# SensorTile_PC.net
KiCad netlist of a schematic drawn in EAGLE
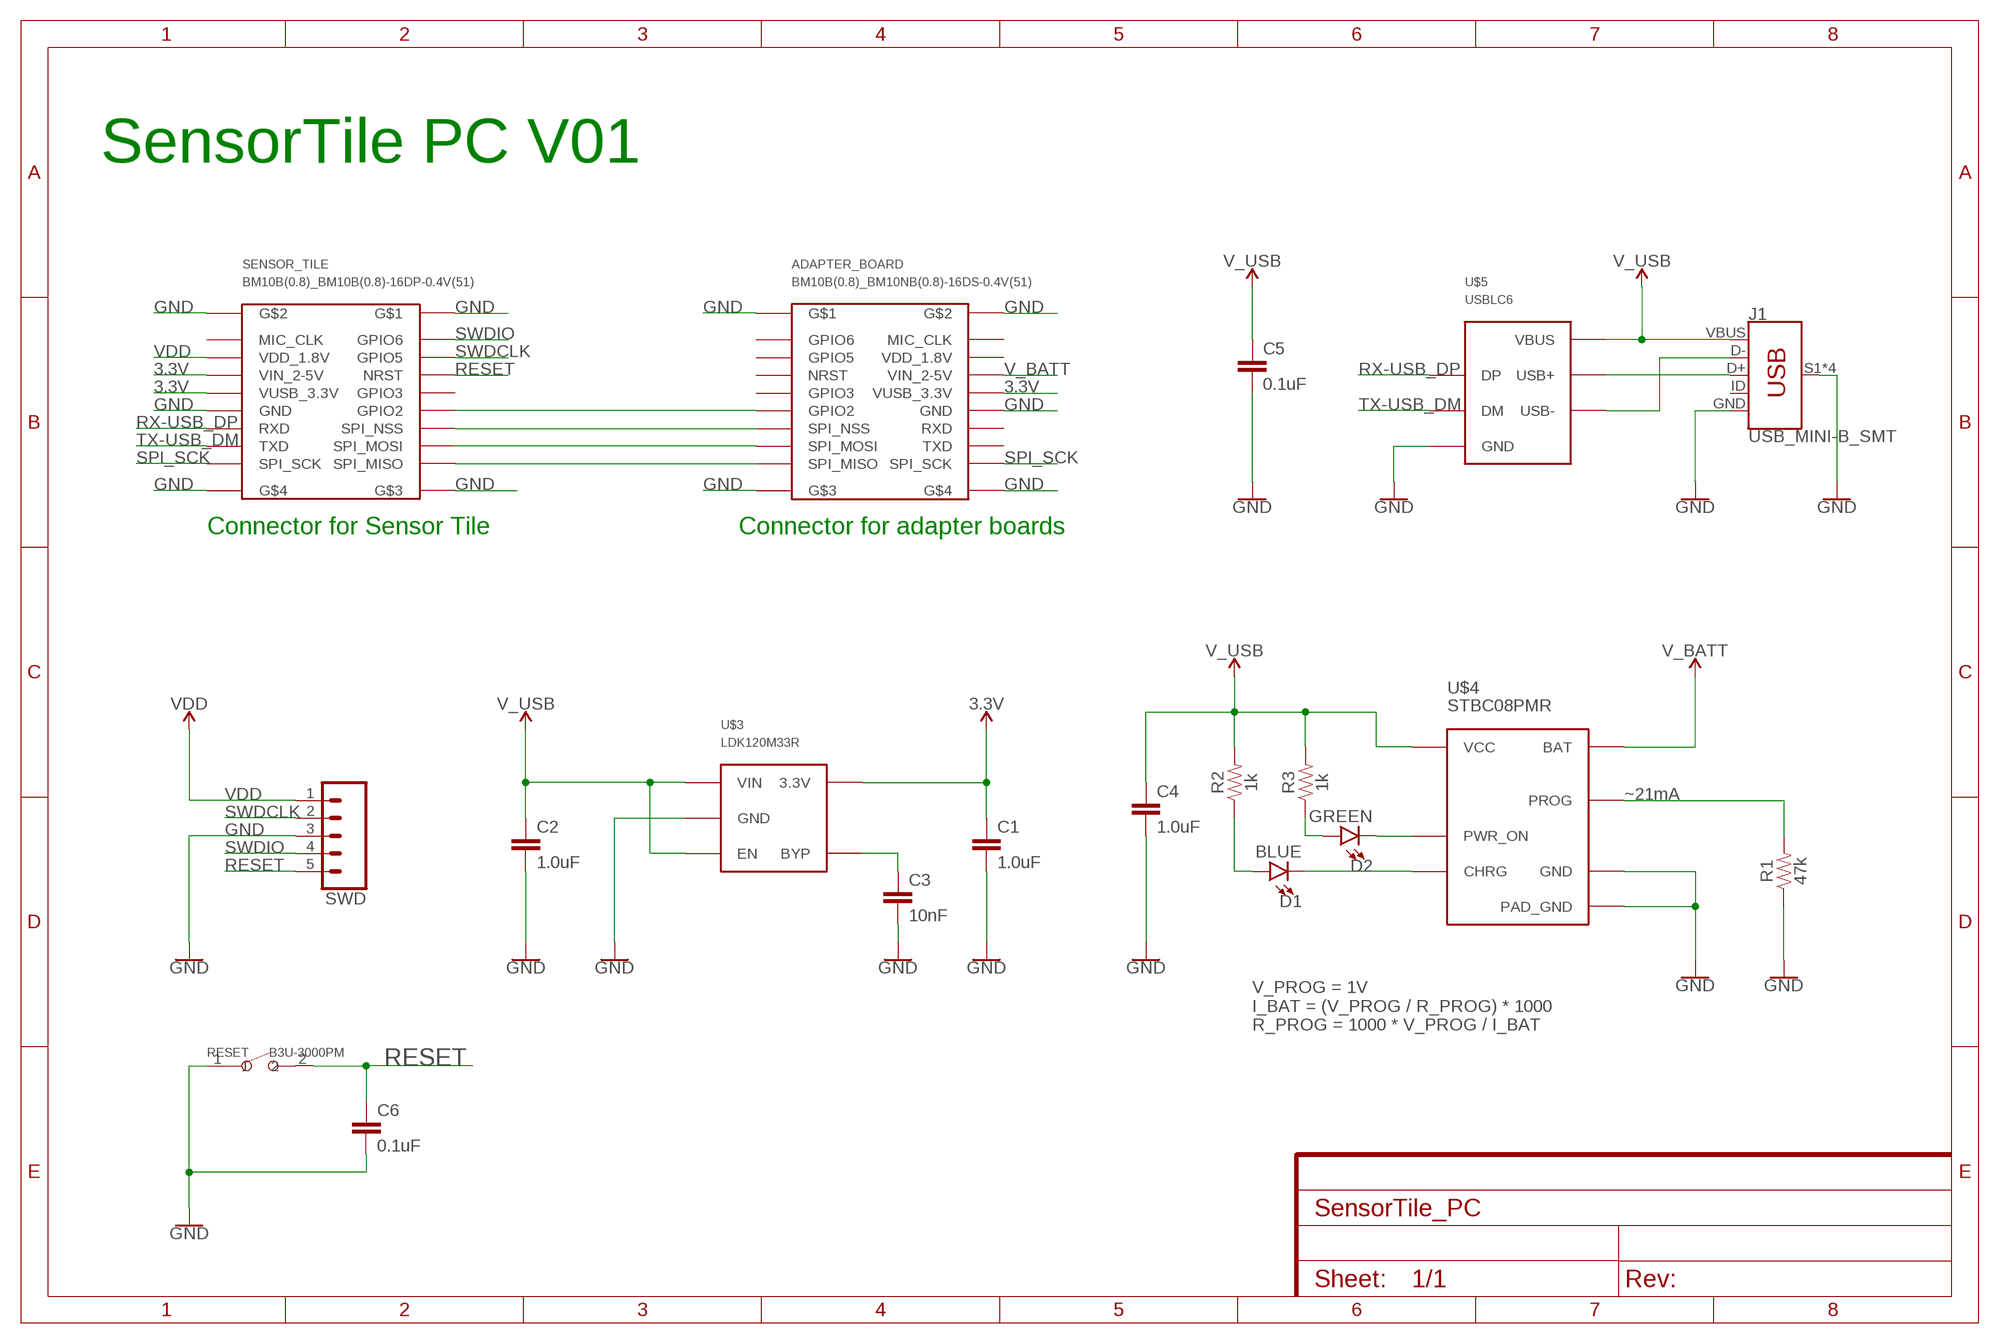
[diagram p0: schematic, sheet 1]

(export (version "E")
  (design (tool "Eeschema 10.0.6"))
  (components
    (comp (ref "ADAPTER_BOARD")
      (value "BM10B(0.8)_BM10NB(0.8)-16DS-0.4V(51)")
      (footprint "eagle-import:BM10B(0.8)_BM10NB(0.8)-16DS-0.4V(51)")
      (libsource (lib "eagle-import") (part "BM10B(0.8)_BM10NB(0.8)-16DS-0.4V(51)"))
    )
    (comp (ref "C1")
      (value "1.0uF")
      (footprint "eagle-import:0603")
      (libsource (lib "eagle-import") (part "1.0UF-0603-16V-10%"))
    )
    (comp (ref "C2")
      (value "1.0uF")
      (footprint "eagle-import:0603")
      (libsource (lib "eagle-import") (part "1.0UF-0603-16V-10%"))
    )
    (comp (ref "C3")
      (value "10nF")
      (footprint "eagle-import:0603")
      (libsource (lib "eagle-import") (part "10NF-0603-50V-10%"))
    )
    (comp (ref "C4")
      (value "1.0uF")
      (footprint "eagle-import:0603")
      (libsource (lib "eagle-import") (part "1.0UF-0603-16V-10%"))
    )
    (comp (ref "C5")
      (value "0.1uF")
      (footprint "eagle-import:0603")
      (libsource (lib "eagle-import") (part "0.1UF-0603-25V-5%"))
    )
    (comp (ref "C6")
      (value "0.1uF")
      (footprint "eagle-import:0603")
      (libsource (lib "eagle-import") (part "0.1UF-0603-25V-5%"))
    )
    (comp (ref "D1")
      (value "BLUE")
      (footprint "eagle-import:LED-0603")
      (libsource (lib "eagle-import") (part "LED-BLUE0603"))
    )
    (comp (ref "D2")
      (value "GREEN")
      (footprint "eagle-import:LED-0603")
      (libsource (lib "eagle-import") (part "LED-GREEN0603"))
    )
    (comp (ref "J1")
      (value "USB_MINI-B_SMT")
      (footprint "eagle-import:USB-MINIB")
      (libsource (lib "eagle-import") (part "USB_MINI-B_SMT"))
    )
    (comp (ref "R1")
      (value "47k")
      (footprint "eagle-import:0603")
      (libsource (lib "eagle-import") (part "47KOHM-0603-1/10W-1%"))
    )
    (comp (ref "R2")
      (value "1k")
      (footprint "eagle-import:0603")
      (libsource (lib "eagle-import") (part "1KOHM-0603-1/10W-1%"))
    )
    (comp (ref "R3")
      (value "1k")
      (footprint "eagle-import:0603")
      (libsource (lib "eagle-import") (part "1KOHM-0603-1/10W-1%"))
    )
    (comp (ref "RESET")
      (value "B3U-3000PM")
      (footprint "eagle-import:SW2-2.6-3.0X2.5X1.2+0.4MM")
      (fields (field (name "MPN") "B3U-1000P-2P-SMD"))
      (libsource (lib "eagle-import") (part "SMD-BUTTON(2P-3.0X2.5X1.2+0.4MM)-B3U-1000P-2P-SMD"))
    )
    (comp (ref "SENSOR_TILE")
      (value "BM10B(0.8)_BM10B(0.8)-16DP-0.4V(51)")
      (footprint "eagle-import:BM10B(0.8)_BM10B(0.8)-16DP-0.4V(51)")
      (libsource (lib "eagle-import") (part "BM10B(0.8)_BM10B(0.8)-16DP-0.4V(51)"))
    )
    (comp (ref "SWD")
      (value "CONN_05")
      (footprint "eagle-import:1X05")
      (libsource (lib "eagle-import") (part "CONN_05"))
    )
    (comp (ref "U$3")
      (value "LDK120M33R")
      (footprint "eagle-import:SOT23-5")
      (libsource (lib "eagle-import") (part "LDK120M33R"))
    )
    (comp (ref "U$4")
      (value "STBC08PMR")
      (footprint "eagle-import:6-DFN(3X3)")
      (libsource (lib "eagle-import") (part "STBC08PMR"))
    )
    (comp (ref "U$5")
      (value "USBLC6")
      (footprint "eagle-import:SOT23-6L")
      (libsource (lib "eagle-import") (part "USBLC6-2SC6"))
    )
  )
  (nets
    (net (code "1") (name "/RESET") (class "Default")
      (node (ref "C6") (pin "1") (pinfunction "1_1") (pintype "passive"))
      (node (ref "RESET") (pin "2") (pinfunction "2_2") (pintype "bidirectional"))
      (node (ref "SENSOR_TILE") (pin "NRST") (pinfunction "NRST_NRST") (pintype "bidirectional"))
      (node (ref "SWD") (pin "5") (pinfunction "5_5") (pintype "passive"))
    )
    (net (code "2") (name "/RX-USB_DP") (class "Default")
      (node (ref "SENSOR_TILE") (pin "RXD") (pinfunction "RXD_RXD") (pintype "bidirectional"))
      (node (ref "U$5") (pin "D+IN$1") (pinfunction "DP_D+IN$1") (pintype "bidirectional"))
    )
    (net (code "3") (name "/SPI_SCK") (class "Default")
      (node (ref "ADAPTER_BOARD") (pin "SPI_SCK") (pinfunction "SPI_SCK_SPI_SCK") (pintype "bidirectional"))
      (node (ref "SENSOR_TILE") (pin "SPI_SCK") (pinfunction "SPI_SCK_SPI_SCK") (pintype "bidirectional"))
    )
    (net (code "4") (name "/SWDCLK") (class "Default")
      (node (ref "SENSOR_TILE") (pin "GPIO5") (pinfunction "GPIO5_GPIO5") (pintype "bidirectional"))
      (node (ref "SWD") (pin "2") (pinfunction "2_2") (pintype "passive"))
    )
    (net (code "5") (name "/SWDIO") (class "Default")
      (node (ref "SENSOR_TILE") (pin "GPIO6") (pinfunction "GPIO6_GPIO6") (pintype "bidirectional"))
      (node (ref "SWD") (pin "4") (pinfunction "4_4") (pintype "passive"))
    )
    (net (code "6") (name "/TX-USB_DM") (class "Default")
      (node (ref "SENSOR_TILE") (pin "TXD") (pinfunction "TXD_TXD") (pintype "bidirectional"))
      (node (ref "U$5") (pin "D-IN$3") (pinfunction "DM_D-IN$3") (pintype "bidirectional"))
    )
    (net (code "7") (name "3.3V") (class "Default")
      (node (ref "ADAPTER_BOARD") (pin "VUSB_3.3V") (pinfunction "VUSB_3.3V_VUSB_3.3V") (pintype "bidirectional"))
      (node (ref "C1") (pin "1") (pinfunction "1_1") (pintype "passive"))
      (node (ref "SENSOR_TILE") (pin "VIN_2-5V") (pinfunction "VIN_2-5V_VIN_2-5V") (pintype "bidirectional"))
      (node (ref "SENSOR_TILE") (pin "VUSB_3.3V") (pinfunction "VUSB_3.3V_VUSB_3.3V") (pintype "bidirectional"))
      (node (ref "U$3") (pin "3V3&5") (pinfunction "3.3V_3V3&5") (pintype "bidirectional"))
    )
    (net (code "8") (name "GND") (class "Default")
      (node (ref "ADAPTER_BOARD") (pin "G$1") (pinfunction "G$1_G$1") (pintype "bidirectional"))
      (node (ref "ADAPTER_BOARD") (pin "G$2") (pinfunction "G$2_G$2") (pintype "bidirectional"))
      (node (ref "ADAPTER_BOARD") (pin "G$3") (pinfunction "G$3_G$3") (pintype "bidirectional"))
      (node (ref "ADAPTER_BOARD") (pin "G$4") (pinfunction "G$4_G$4") (pintype "bidirectional"))
      (node (ref "ADAPTER_BOARD") (pin "GND$1") (pinfunction "GND_GND$1") (pintype "bidirectional"))
      (node (ref "C1") (pin "2") (pinfunction "2_2") (pintype "passive"))
      (node (ref "C2") (pin "2") (pinfunction "2_2") (pintype "passive"))
      (node (ref "C3") (pin "2") (pinfunction "2_2") (pintype "passive"))
      (node (ref "C4") (pin "2") (pinfunction "2_2") (pintype "passive"))
      (node (ref "C5") (pin "2") (pinfunction "2_2") (pintype "passive"))
      (node (ref "C6") (pin "2") (pinfunction "2_2") (pintype "passive"))
      (node (ref "J1") (pin "GND") (pinfunction "GND_GND") (pintype "power_in"))
      (node (ref "J1") (pin "S1") (pinfunction "SHIELD_S1") (pintype "bidirectional"))
      (node (ref "J1") (pin "S2") (pinfunction "SHIELD_S2") (pintype "bidirectional"))
      (node (ref "J1") (pin "S3") (pinfunction "SHIELD_S3") (pintype "bidirectional"))
      (node (ref "J1") (pin "S4") (pinfunction "SHIELD_S4") (pintype "bidirectional"))
      (node (ref "R1") (pin "1") (pinfunction "1_1") (pintype "passive"))
      (node (ref "RESET") (pin "1") (pinfunction "1_1") (pintype "bidirectional"))
      (node (ref "SENSOR_TILE") (pin "G$1") (pinfunction "G$1_G$1") (pintype "bidirectional"))
      (node (ref "SENSOR_TILE") (pin "G$2") (pinfunction "G$2_G$2") (pintype "bidirectional"))
      (node (ref "SENSOR_TILE") (pin "G$3") (pinfunction "G$3_G$3") (pintype "bidirectional"))
      (node (ref "SENSOR_TILE") (pin "G$4") (pinfunction "G$4_G$4") (pintype "bidirectional"))
      (node (ref "SENSOR_TILE") (pin "GND$1") (pinfunction "GND_GND$1") (pintype "bidirectional"))
      (node (ref "SWD") (pin "3") (pinfunction "3_3") (pintype "passive"))
      (node (ref "U$3") (pin "GND$2") (pinfunction "GND_GND$2") (pintype "bidirectional"))
      (node (ref "U$4") (pin "GND$4") (pinfunction "GND_GND$4") (pintype "bidirectional"))
      (node (ref "U$4") (pin "PAD_GND$7") (pinfunction "PAD_GND_PAD_GND$7") (pintype "bidirectional"))
      (node (ref "U$5") (pin "GND$2") (pinfunction "GND_GND$2") (pintype "bidirectional"))
    )
    (net (code "9") (name "Net-(ADAPTER_BOARD-PadGPIO2)") (class "Default")
      (node (ref "ADAPTER_BOARD") (pin "GPIO2") (pinfunction "GPIO2_GPIO2") (pintype "bidirectional"))
      (node (ref "SENSOR_TILE") (pin "GPIO2") (pinfunction "GPIO2_GPIO2") (pintype "bidirectional"))
    )
    (net (code "10") (name "Net-(ADAPTER_BOARD-PadSPI_MISO)") (class "Default")
      (node (ref "ADAPTER_BOARD") (pin "SPI_MISO") (pinfunction "SPI_MISO_SPI_MISO") (pintype "bidirectional"))
      (node (ref "SENSOR_TILE") (pin "SPI_MISO") (pinfunction "SPI_MISO_SPI_MISO") (pintype "bidirectional"))
    )
    (net (code "11") (name "Net-(ADAPTER_BOARD-PadSPI_MOSI)") (class "Default")
      (node (ref "ADAPTER_BOARD") (pin "SPI_MOSI") (pinfunction "SPI_MOSI_SPI_MOSI") (pintype "bidirectional"))
      (node (ref "SENSOR_TILE") (pin "SPI_MOSI") (pinfunction "SPI_MOSI_SPI_MOSI") (pintype "bidirectional"))
    )
    (net (code "12") (name "Net-(ADAPTER_BOARD-PadSPI_NSS)") (class "Default")
      (node (ref "ADAPTER_BOARD") (pin "SPI_NSS") (pinfunction "SPI_NSS_SPI_NSS") (pintype "bidirectional"))
      (node (ref "SENSOR_TILE") (pin "SPI_NSS") (pinfunction "SPI_NSS_SPI_NSS") (pintype "bidirectional"))
    )
    (net (code "13") (name "Net-(D1-PadA)") (class "Default")
      (node (ref "D1") (pin "A") (pinfunction "A_A") (pintype "passive"))
      (node (ref "R2") (pin "1") (pinfunction "1_1") (pintype "passive"))
    )
    (net (code "14") (name "Net-(D2-PadA)") (class "Default")
      (node (ref "D2") (pin "A") (pinfunction "A_A") (pintype "passive"))
      (node (ref "R3") (pin "1") (pinfunction "1_1") (pintype "passive"))
    )
    (net (code "15") (name "Net-(U$3-BYP)") (class "Default")
      (node (ref "C3") (pin "1") (pinfunction "1_1") (pintype "passive"))
      (node (ref "U$3") (pin "BYP$4") (pinfunction "BYP_BYP$4") (pintype "bidirectional"))
    )
    (net (code "16") (name "Net-(U$4-CHRG)") (class "Default")
      (node (ref "D1") (pin "C") (pinfunction "C_C") (pintype "passive"))
      (node (ref "U$4") (pin "CHRG$3") (pinfunction "CHRG_CHRG$3") (pintype "bidirectional"))
    )
    (net (code "17") (name "Net-(U$4-PROG)") (class "Default")
      (node (ref "R1") (pin "2") (pinfunction "2_2") (pintype "passive"))
      (node (ref "U$4") (pin "PROG$5") (pinfunction "PROG_PROG$5") (pintype "bidirectional"))
    )
    (net (code "18") (name "Net-(U$4-PWR_ON)") (class "Default")
      (node (ref "D2") (pin "C") (pinfunction "C_C") (pintype "passive"))
      (node (ref "U$4") (pin "ON$2") (pinfunction "PWR_ON_ON$2") (pintype "bidirectional"))
    )
    (net (code "19") (name "Net-(U$5-USB+)") (class "Default")
      (node (ref "J1") (pin "D+") (pinfunction "D+_D+") (pintype "bidirectional"))
      (node (ref "U$5") (pin "D+OUT$1$6") (pinfunction "USB+_D+OUT$1$6") (pintype "bidirectional"))
    )
    (net (code "20") (name "Net-(U$5-USB-)") (class "Default")
      (node (ref "J1") (pin "D-") (pinfunction "D-_D-") (pintype "bidirectional"))
      (node (ref "U$5") (pin "D-OUT$1$4") (pinfunction "USB-_D-OUT$1$4") (pintype "bidirectional"))
    )
    (net (code "21") (name "VDD") (class "Default")
      (node (ref "SENSOR_TILE") (pin "VDD_1.8V") (pinfunction "VDD_1.8V_VDD_1.8V") (pintype "bidirectional"))
      (node (ref "SWD") (pin "1") (pinfunction "1_1") (pintype "passive"))
    )
    (net (code "22") (name "V_BATT") (class "Default")
      (node (ref "ADAPTER_BOARD") (pin "VIN_2-5V") (pinfunction "VIN_2-5V_VIN_2-5V") (pintype "bidirectional"))
      (node (ref "U$4") (pin "BAT$1") (pinfunction "BAT_BAT$1") (pintype "bidirectional"))
    )
    (net (code "23") (name "V_USB") (class "Default")
      (node (ref "C2") (pin "1") (pinfunction "1_1") (pintype "passive"))
      (node (ref "C4") (pin "1") (pinfunction "1_1") (pintype "passive"))
      (node (ref "C5") (pin "1") (pinfunction "1_1") (pintype "passive"))
      (node (ref "J1") (pin "VBUS") (pinfunction "VBUS_VBUS") (pintype "power_in"))
      (node (ref "R2") (pin "2") (pinfunction "2_2") (pintype "passive"))
      (node (ref "R3") (pin "2") (pinfunction "2_2") (pintype "passive"))
      (node (ref "U$3") (pin "EN$3") (pinfunction "EN_EN$3") (pintype "bidirectional"))
      (node (ref "U$3") (pin "VIN$1") (pinfunction "VIN_VIN$1") (pintype "bidirectional"))
      (node (ref "U$4") (pin "VCC$6") (pinfunction "VCC_VCC$6") (pintype "bidirectional"))
      (node (ref "U$5") (pin "VUSB$5") (pinfunction "VBUS_VUSB$5") (pintype "bidirectional"))
    )
    (net (code "24") (name "unconnected-(ADAPTER_BOARD-PadGPIO3)") (class "Default")
      (node (ref "ADAPTER_BOARD") (pin "GPIO3") (pinfunction "GPIO3_GPIO3") (pintype "bidirectional"))
    )
    (net (code "25") (name "unconnected-(ADAPTER_BOARD-PadGPIO5)") (class "Default")
      (node (ref "ADAPTER_BOARD") (pin "GPIO5") (pinfunction "GPIO5_GPIO5") (pintype "bidirectional"))
    )
    (net (code "26") (name "unconnected-(ADAPTER_BOARD-PadGPIO6)") (class "Default")
      (node (ref "ADAPTER_BOARD") (pin "GPIO6") (pinfunction "GPIO6_GPIO6") (pintype "bidirectional"))
    )
    (net (code "27") (name "unconnected-(ADAPTER_BOARD-PadMIC_CLK)") (class "Default")
      (node (ref "ADAPTER_BOARD") (pin "MIC_CLK") (pinfunction "MIC_CLK_MIC_CLK") (pintype "bidirectional"))
    )
    (net (code "28") (name "unconnected-(ADAPTER_BOARD-PadNRST)") (class "Default")
      (node (ref "ADAPTER_BOARD") (pin "NRST") (pinfunction "NRST_NRST") (pintype "bidirectional"))
    )
    (net (code "29") (name "unconnected-(ADAPTER_BOARD-PadRXD)") (class "Default")
      (node (ref "ADAPTER_BOARD") (pin "RXD") (pinfunction "RXD_RXD") (pintype "bidirectional"))
    )
    (net (code "30") (name "unconnected-(ADAPTER_BOARD-PadTXD)") (class "Default")
      (node (ref "ADAPTER_BOARD") (pin "TXD") (pinfunction "TXD_TXD") (pintype "bidirectional"))
    )
    (net (code "31") (name "unconnected-(ADAPTER_BOARD-PadVDD_1.8V)") (class "Default")
      (node (ref "ADAPTER_BOARD") (pin "VDD_1.8V") (pinfunction "VDD_1.8V_VDD_1.8V") (pintype "bidirectional"))
    )
    (net (code "32") (name "unconnected-(J1-PadID)") (class "Default")
      (node (ref "J1") (pin "ID") (pinfunction "ID_ID") (pintype "bidirectional"))
    )
    (net (code "33") (name "unconnected-(SENSOR_TILE-PadGPIO3)") (class "Default")
      (node (ref "SENSOR_TILE") (pin "GPIO3") (pinfunction "GPIO3_GPIO3") (pintype "bidirectional"))
    )
    (net (code "34") (name "unconnected-(SENSOR_TILE-PadMIC_CLK)") (class "Default")
      (node (ref "SENSOR_TILE") (pin "MIC_CLK") (pinfunction "MIC_CLK_MIC_CLK") (pintype "bidirectional"))
    )
  )
)
